# 425AK01A_S01.net
KiCad netlist of a schematic drawn in Altium Designer
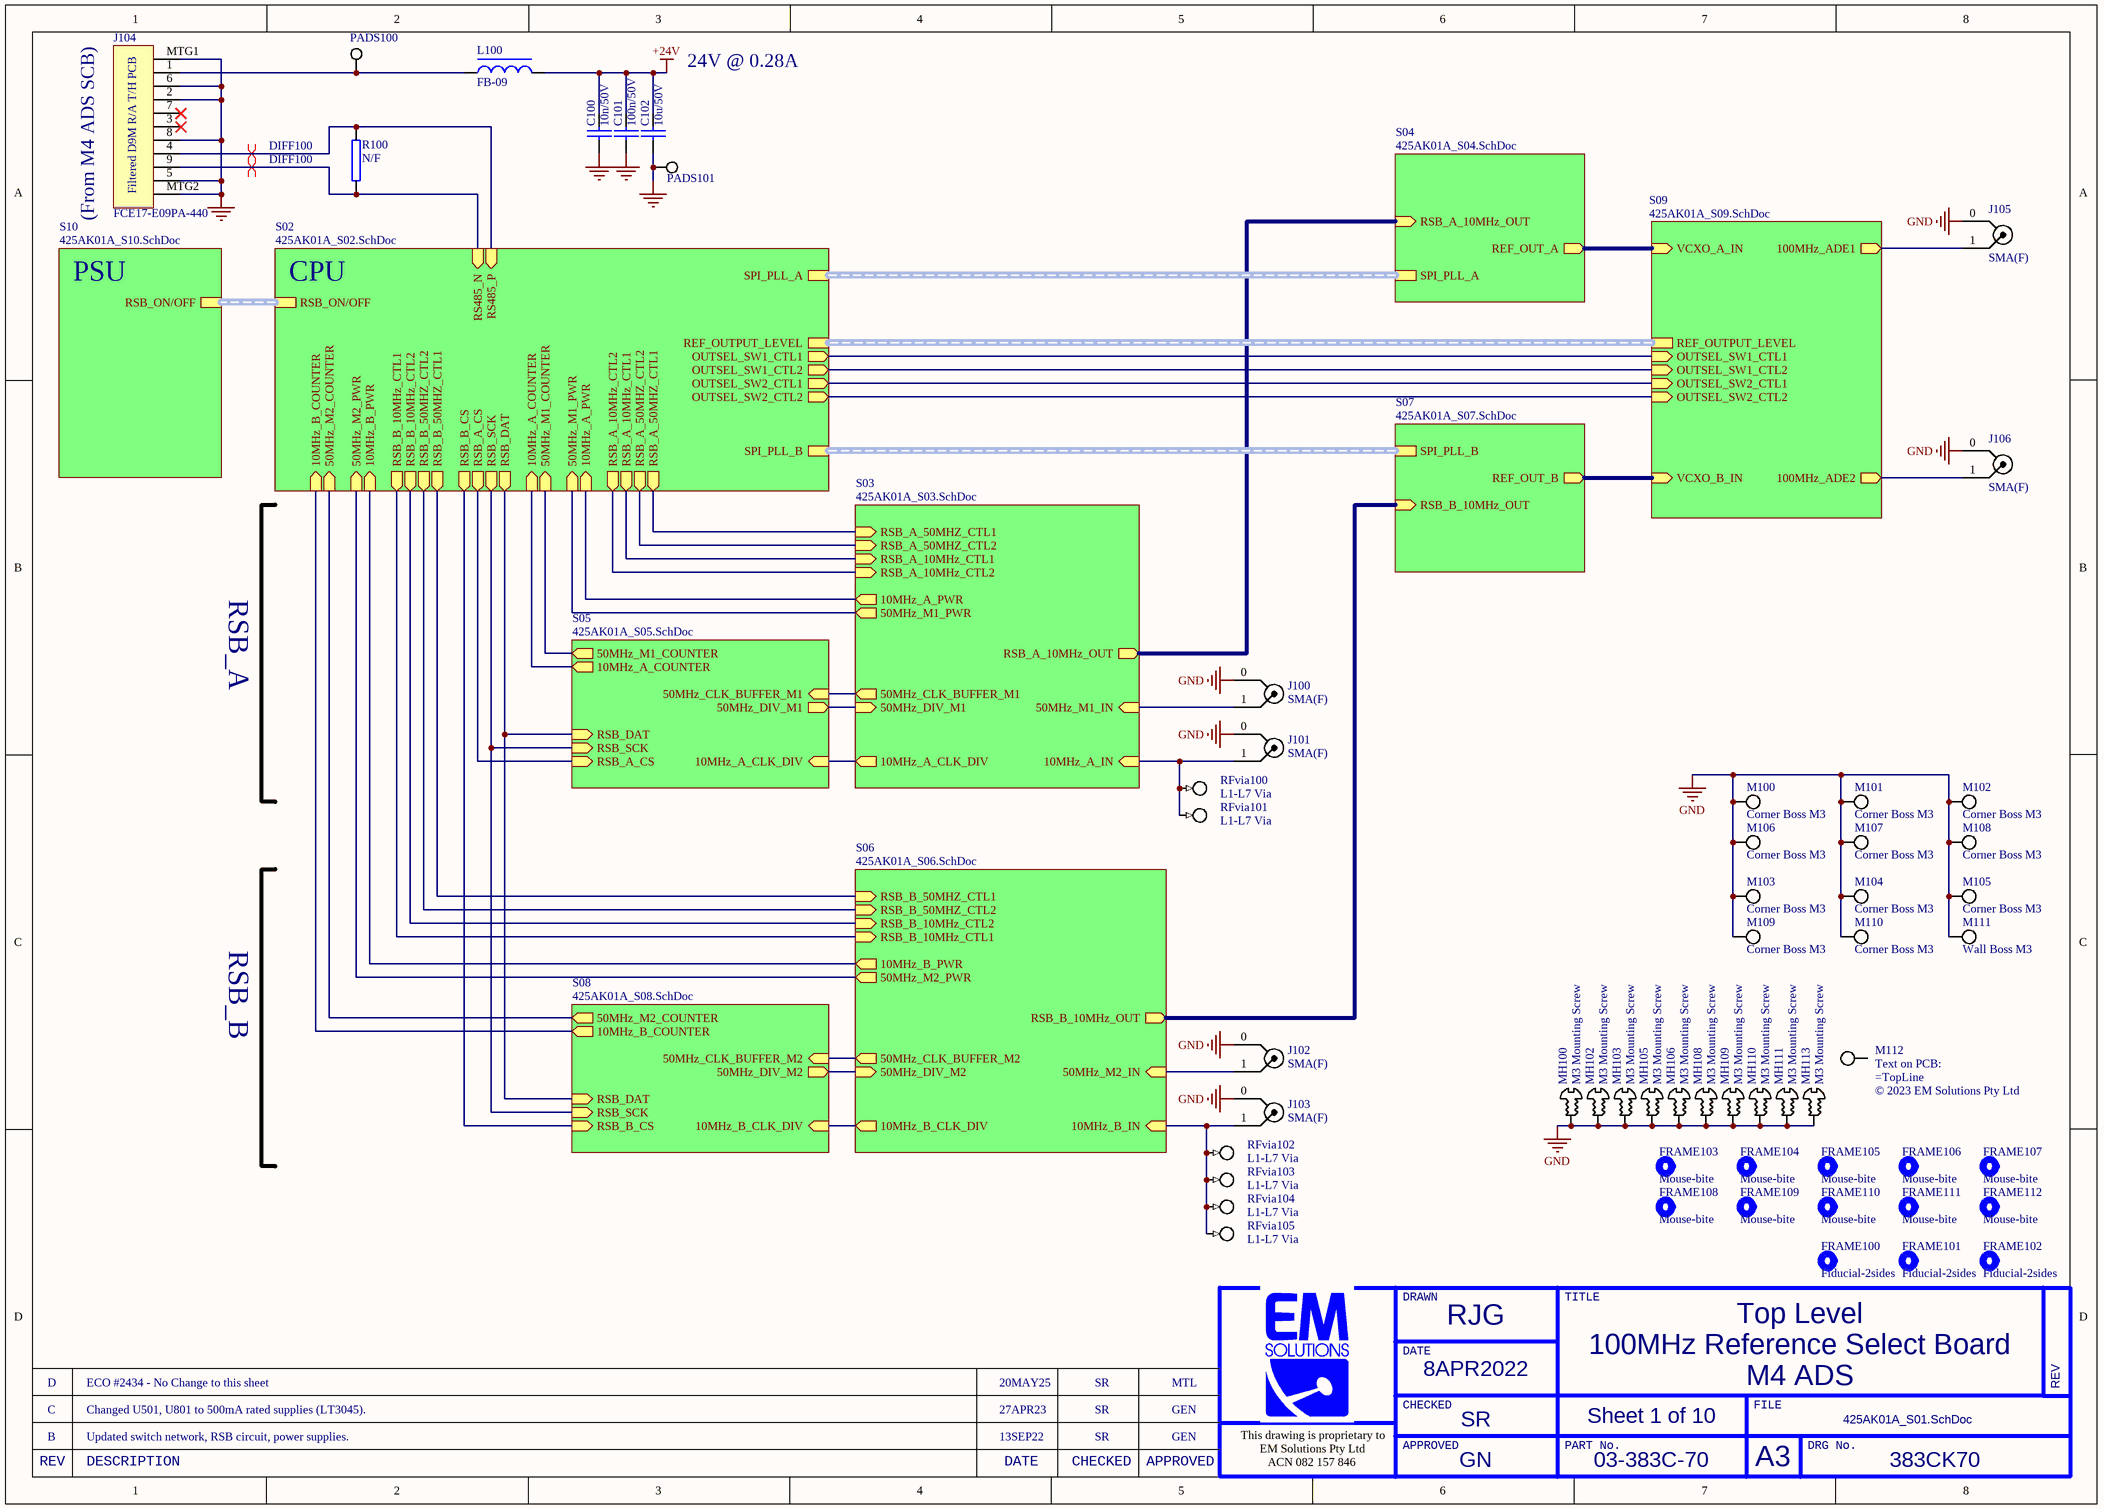
[diagram p0: 425AK01A_S01.SchDoc]

(export (version "E")
  (design (tool "Eeschema 10.0.6"))
  (components
    (comp (ref "C100")
      (value "10n/50V")
      (footprint "0402C")
      (description "Capacitor, 0402, 10n X7R 10% 50V Ceramic, NiSn")
      (fields (field (name "PART NUMBER") "41-010N-12") (field (name "MANUFACTURER") "MURATA"))
      (libsource (lib "EM DFM Library") (part "CAP"))
    )
    (comp (ref "C101")
      (value "100n/50V")
      (footprint "0402C")
      (description "Capacitor, 0402, 100n, X7R, 10% 50V, Ceramic")
      (fields (field (name "PART NUMBER") "41-100N-13") (field (name "MANUFACTURER") "MURATA"))
      (libsource (lib "EM DFM Library") (part "CAP"))
    )
    (comp (ref "C102")
      (value "10u/50V")
      (footprint "1206C")
      (description "Capacitor, 1206, 10u X7R 10% 50V Ceramic, NiSn")
      (fields (field (name "PART NUMBER") "41-010U-13") (field (name "MANUFACTURER") "SAMSUNG"))
      (libsource (lib "EM DFM Library") (part "CAP"))
    )
    (comp (ref "FRAME100")
      (value "Fiducial-2sides")
      (footprint "Fiducial-2layers")
      (description "Fiducial on both sides of the PCB")
      (libsource (lib "Russell") (part "Fiducial-2sides"))
    )
    (comp (ref "FRAME101")
      (value "Fiducial-2sides")
      (footprint "Fiducial-2layers")
      (description "Fiducial on both sides of the PCB")
      (libsource (lib "Russell") (part "Fiducial-2sides"))
    )
    (comp (ref "FRAME102")
      (value "Fiducial-2sides")
      (footprint "Fiducial-2layers")
      (description "Fiducial on both sides of the PCB")
      (libsource (lib "Russell") (part "Fiducial-2sides"))
    )
    (comp (ref "FRAME103")
      (value "Mouse-bite")
      (footprint "Breakout-3hole")
      (description "Add design rule:\r\nBoardOutlineClearance_Breakouts, name like 'FRAME*-NoDRC', 0")
      (libsource (lib "Russell") (part "Breakout"))
    )
    (comp (ref "FRAME104")
      (value "Mouse-bite")
      (footprint "Breakout-3hole")
      (description "Add design rule:\r\nBoardOutlineClearance_Breakouts, name like 'FRAME*-NoDRC', 0")
      (libsource (lib "Russell") (part "Breakout"))
    )
    (comp (ref "FRAME105")
      (value "Mouse-bite")
      (footprint "Breakout-3hole")
      (description "Add design rule:\r\nBoardOutlineClearance_Breakouts, name like 'FRAME*-NoDRC', 0")
      (libsource (lib "Russell") (part "Breakout"))
    )
    (comp (ref "FRAME106")
      (value "Mouse-bite")
      (footprint "Breakout-3hole")
      (description "Add design rule:\r\nBoardOutlineClearance_Breakouts, name like 'FRAME*-NoDRC', 0")
      (libsource (lib "Russell") (part "Breakout"))
    )
    (comp (ref "FRAME107")
      (value "Mouse-bite")
      (footprint "Breakout-3hole")
      (description "Add design rule:\r\nBoardOutlineClearance_Breakouts, name like 'FRAME*-NoDRC', 0")
      (libsource (lib "Russell") (part "Breakout"))
    )
    (comp (ref "FRAME108")
      (value "Mouse-bite")
      (footprint "Breakout-3hole")
      (description "Add design rule:\r\nBoardOutlineClearance_Breakouts, name like 'FRAME*-NoDRC', 0")
      (libsource (lib "Russell") (part "Breakout"))
    )
    (comp (ref "FRAME109")
      (value "Mouse-bite")
      (footprint "Breakout-3hole")
      (description "Add design rule:\r\nBoardOutlineClearance_Breakouts, name like 'FRAME*-NoDRC', 0")
      (libsource (lib "Russell") (part "Breakout"))
    )
    (comp (ref "FRAME110")
      (value "Mouse-bite")
      (footprint "Breakout-3hole")
      (description "Add design rule:\r\nBoardOutlineClearance_Breakouts, name like 'FRAME*-NoDRC', 0")
      (libsource (lib "Russell") (part "Breakout"))
    )
    (comp (ref "FRAME111")
      (value "Mouse-bite")
      (footprint "Breakout-3hole")
      (description "Add design rule:\r\nBoardOutlineClearance_Breakouts, name like 'FRAME*-NoDRC', 0")
      (libsource (lib "Russell") (part "Breakout"))
    )
    (comp (ref "FRAME112")
      (value "Mouse-bite")
      (footprint "Breakout-3hole")
      (description "Add design rule:\r\nBoardOutlineClearance_Breakouts, name like 'FRAME*-NoDRC', 0")
      (libsource (lib "Russell") (part "Breakout"))
    )
    (comp (ref "J100")
      (value "SMA(F)")
      (footprint "SMA-flange-generic")
      (description "Generic SMA bulkhead connector. Grounding via chassis.")
      (fields (field (name "PART NUMBER") "30-P-01"))
      (libsource (lib "Russell") (part "Connector-SMA-edge"))
    )
    (comp (ref "J101")
      (value "SMA(F)")
      (footprint "SMA-flange-generic")
      (description "Generic SMA bulkhead connector. Grounding via chassis.")
      (fields (field (name "PART NUMBER") "30-P-01"))
      (libsource (lib "Russell") (part "Connector-SMA-edge"))
    )
    (comp (ref "J102")
      (value "SMA(F)")
      (footprint "SMA-flange-generic")
      (description "Generic SMA bulkhead connector. Grounding via chassis.")
      (fields (field (name "PART NUMBER") "30-P-01"))
      (libsource (lib "Russell") (part "Connector-SMA-edge"))
    )
    (comp (ref "J103")
      (value "SMA(F)")
      (footprint "SMA-flange-generic")
      (description "Generic SMA bulkhead connector. Grounding via chassis.")
      (fields (field (name "PART NUMBER") "30-P-01"))
      (libsource (lib "Russell") (part "Connector-SMA-edge"))
    )
    (comp (ref "J104")
      (value "FCE17-E09PA-440")
      (footprint "Connector-D9-M-Filtered-T/H")
      (description "Amphenol FCE17-E09PA-440 D9M Filtered R/A T/H connector")
      (fields (field (name "PART NUMBER") "20-D9-10"))
      (libsource (lib "Russell") (part "Connector-D9-M-Filtered-T/H_PCBorder"))
    )
    (comp (ref "J105")
      (value "SMA(F)")
      (footprint "SMA-flange-generic")
      (description "Generic SMA bulkhead connector. Grounding via chassis.")
      (fields (field (name "PART NUMBER") "30-P-01"))
      (libsource (lib "Russell") (part "Connector-SMA-edge"))
    )
    (comp (ref "J106")
      (value "SMA(F)")
      (footprint "SMA-flange-generic")
      (description "Generic SMA bulkhead connector. Grounding via chassis.")
      (fields (field (name "PART NUMBER") "30-P-01"))
      (libsource (lib "Russell") (part "Connector-SMA-edge"))
    )
    (comp (ref "L100")
      (value "FB-09")
      (footprint "0805L")
      (description "Solid Inductor, 1000ohm@100MHz, DCR=0.15, 1A, 0805 size")
      (fields (field (name "PART NUMBER") "46-B-09") (field (name "MANUFACTURER") "LAIRD"))
      (libsource (lib "EM DFM Library") (part "IND"))
    )
    (comp (ref "M100")
      (value "Corner Boss M3")
      (footprint "Boss-corner-M3")
      (libsource (lib "Russell") (part "Boss-Corner-M3"))
    )
    (comp (ref "M101")
      (value "Corner Boss M3")
      (footprint "Boss-corner-M3")
      (libsource (lib "Russell") (part "Boss-Corner-M3"))
    )
    (comp (ref "M102")
      (value "Corner Boss M3")
      (footprint "Boss-corner-M3-rev")
      (libsource (lib "Russell") (part "Boss-Corner-M3"))
    )
    (comp (ref "M103")
      (value "Corner Boss M3")
      (footprint "Boss-corner-M3-rev")
      (libsource (lib "Russell") (part "Boss-Corner-M3"))
    )
    (comp (ref "M104")
      (value "Corner Boss M3")
      (footprint "Boss-corner-M3")
      (libsource (lib "Russell") (part "Boss-Corner-M3"))
    )
    (comp (ref "M105")
      (value "Corner Boss M3")
      (footprint "Boss-corner-M3-rev")
      (libsource (lib "Russell") (part "Boss-Corner-M3"))
    )
    (comp (ref "M106")
      (value "Corner Boss M3")
      (footprint "Boss-corner-M3")
      (libsource (lib "Russell") (part "Boss-Corner-M3"))
    )
    (comp (ref "M107")
      (value "Corner Boss M3")
      (footprint "Boss-corner-M3")
      (libsource (lib "Russell") (part "Boss-Corner-M3"))
    )
    (comp (ref "M108")
      (value "Corner Boss M3")
      (footprint "Boss-corner-M3")
      (libsource (lib "Russell") (part "Boss-Corner-M3"))
    )
    (comp (ref "M109")
      (value "Corner Boss M3")
      (footprint "Boss-corner-M3")
      (libsource (lib "Russell") (part "Boss-Corner-M3"))
    )
    (comp (ref "M110")
      (value "Corner Boss M3")
      (footprint "Boss-corner-M3")
      (libsource (lib "Russell") (part "Boss-Corner-M3"))
    )
    (comp (ref "M111")
      (value "Wall Boss M3")
      (footprint "Boss-Wall")
      (libsource (lib "Russell") (part "Boss-M3-Wall"))
    )
    (comp (ref "M112")
      (value "Text on PCB:")
      (footprint "PCB-title-V2-3mm")
      (libsource (lib "Russell") (part "Title of PCB"))
    )
    (comp (ref "MH100")
      (value "M3 Mounting Screw")
      (footprint "M3_SCREW")
      (libsource (lib "Russell") (part "M3 Screw"))
    )
    (comp (ref "MH102")
      (value "M3 Mounting Screw")
      (footprint "M3_SCREW")
      (libsource (lib "Russell") (part "M3 Screw"))
    )
    (comp (ref "MH103")
      (value "M3 Mounting Screw")
      (footprint "M3_SCREW")
      (libsource (lib "Russell") (part "M3 Screw"))
    )
    (comp (ref "MH105")
      (value "M3 Mounting Screw")
      (footprint "M3_SCREW")
      (libsource (lib "Russell") (part "M3 Screw"))
    )
    (comp (ref "MH106")
      (value "M3 Mounting Screw")
      (footprint "M3_SCREW")
      (libsource (lib "Russell") (part "M3 Screw"))
    )
    (comp (ref "MH108")
      (value "M3 Mounting Screw")
      (footprint "M3_SCREW")
      (libsource (lib "Russell") (part "M3 Screw"))
    )
    (comp (ref "MH109")
      (value "M3 Mounting Screw")
      (footprint "M3_SCREW")
      (libsource (lib "Russell") (part "M3 Screw"))
    )
    (comp (ref "MH110")
      (value "M3 Mounting Screw")
      (footprint "M3_SCREW")
      (libsource (lib "Russell") (part "M3 Screw"))
    )
    (comp (ref "MH111")
      (value "M3 Mounting Screw")
      (footprint "M3_SCREW")
      (libsource (lib "Russell") (part "M3 Screw"))
    )
    (comp (ref "MH113")
      (value "M3 Mounting Screw")
      (footprint "M3_SCREW")
      (libsource (lib "Russell") (part "M3 Screw"))
    )
    (comp (ref "PADS100")
      (value "Pads")
      (footprint "Pads-1x3-V3-0.3/0.6mm")
      (description "Cluster of pads")
      (libsource (lib "Russell") (part "Pads"))
    )
    (comp (ref "PADS101")
      (value "Pads")
      (footprint "Pads-1x3-V3-0.3/0.6mm")
      (description "Cluster of pads")
      (libsource (lib "Russell") (part "Pads"))
    )
    (comp (ref "R100")
      (value "N/F")
      (footprint "0805")
      (description "Resistor, 0805, SOT, Not Fitted")
      (fields (field (name "PART NUMBER") "44-N/F-09") (field (name "MANUFACTURER") "PHILIPS"))
      (libsource (lib "EM DFM Library") (part "RES"))
    )
    (comp (ref "RFvia100")
      (value "L1-L7 Via")
      (footprint "RFvia_L1-L7")
      (description "RF Via from layer 1 to layer 7, on an 8-layer board.")
      (libsource (lib "RFvias-8layer") (part "RFvia_L1-L7"))
    )
    (comp (ref "RFvia101")
      (value "L1-L7 Via")
      (footprint "RFvia_L1-L7")
      (description "RF Via from layer 1 to layer 7, on an 8-layer board.")
      (libsource (lib "RFvias-8layer") (part "RFvia_L1-L7"))
    )
    (comp (ref "RFvia102")
      (value "L1-L7 Via")
      (footprint "RFvia_L1-L7")
      (description "RF Via from layer 1 to layer 7, on an 8-layer board.")
      (libsource (lib "RFvias-8layer") (part "RFvia_L1-L7"))
    )
    (comp (ref "RFvia103")
      (value "L1-L7 Via")
      (footprint "RFvia_L1-L7")
      (description "RF Via from layer 1 to layer 7, on an 8-layer board.")
      (libsource (lib "RFvias-8layer") (part "RFvia_L1-L7"))
    )
    (comp (ref "RFvia104")
      (value "L1-L7 Via")
      (footprint "RFvia_L1-L7")
      (description "RF Via from layer 1 to layer 7, on an 8-layer board.")
      (libsource (lib "RFvias-8layer") (part "RFvia_L1-L7"))
    )
    (comp (ref "RFvia105")
      (value "L1-L7 Via")
      (footprint "RFvia_L1-L7")
      (description "RF Via from layer 1 to layer 7, on an 8-layer board.")
      (libsource (lib "RFvias-8layer") (part "RFvia_L1-L7"))
    )
  )
  (nets
    (net (code "1") (name "+24V") (class "Default")
      (node (ref "C100") (pin "1") (pintype "passive"))
      (node (ref "C101") (pin "1") (pintype "passive"))
      (node (ref "C102") (pin "1") (pintype "passive"))
      (node (ref "L100") (pin "2") (pinfunction "2_2") (pintype "passive"))
    )
    (net (code "4") (name "/10MHz_A_IN") (class "Default")
      (node (ref "J101") (pin "1") (pinfunction "1_1") (pintype "passive"))
      (node (ref "RFvia100") (pin "1") (pinfunction "1_1") (pintype "input"))
      (node (ref "RFvia101") (pin "1") (pinfunction "1_1") (pintype "input"))
    )
    (net (code "8") (name "/10MHz_B_IN") (class "Default")
      (node (ref "J103") (pin "1") (pinfunction "1_1") (pintype "passive"))
      (node (ref "RFvia102") (pin "1") (pinfunction "1_1") (pintype "input"))
      (node (ref "RFvia103") (pin "1") (pinfunction "1_1") (pintype "input"))
      (node (ref "RFvia104") (pin "1") (pinfunction "1_1") (pintype "input"))
      (node (ref "RFvia105") (pin "1") (pinfunction "1_1") (pintype "input"))
    )
    (net (code "15") (name "/50MHz_M1_IN") (class "Default")
      (node (ref "J100") (pin "1") (pinfunction "1_1") (pintype "passive"))
    )
    (net (code "18") (name "/50MHz_M2_IN") (class "Default")
      (node (ref "J102") (pin "1") (pinfunction "1_1") (pintype "passive"))
    )
    (net (code "20") (name "/100MHz_ADE1") (class "Default")
      (node (ref "J105") (pin "1") (pinfunction "1_1") (pintype "passive"))
    )
    (net (code "21") (name "/100MHz_ADE2") (class "Default")
      (node (ref "J106") (pin "1") (pinfunction "1_1") (pintype "passive"))
    )
    (net (code "29") (name "/RS485_N") (class "Default")
      (node (ref "J104") (pin "9") (pinfunction "9_9") (pintype "passive"))
      (node (ref "R100") (pin "1") (pintype "passive"))
    )
    (net (code "30") (name "/RS485_P") (class "Default")
      (node (ref "J104") (pin "4") (pinfunction "4_4") (pintype "passive"))
      (node (ref "R100") (pin "2") (pintype "passive"))
    )
    (net (code "48") (name "GND") (class "Default")
      (node (ref "C100") (pin "2") (pintype "passive"))
      (node (ref "C101") (pin "2") (pintype "passive"))
      (node (ref "C102") (pin "2") (pintype "passive"))
      (node (ref "J100") (pin "0") (pinfunction "0_0") (pintype "passive"))
      (node (ref "J101") (pin "0") (pinfunction "0_0") (pintype "passive"))
      (node (ref "J102") (pin "0") (pinfunction "0_0") (pintype "passive"))
      (node (ref "J103") (pin "0") (pinfunction "0_0") (pintype "passive"))
      (node (ref "J104") (pin "2") (pinfunction "2_2") (pintype "passive"))
      (node (ref "J104") (pin "5") (pinfunction "5_5") (pintype "passive"))
      (node (ref "J104") (pin "6") (pinfunction "6_6") (pintype "passive"))
      (node (ref "J104") (pin "8") (pinfunction "8_8") (pintype "passive"))
      (node (ref "J104") (pin "MTG1") (pinfunction "MTG1_MTG1") (pintype "passive"))
      (node (ref "J104") (pin "MTG2") (pinfunction "MTG2_MTG2") (pintype "passive"))
      (node (ref "J105") (pin "0") (pinfunction "0_0") (pintype "passive"))
      (node (ref "J106") (pin "0") (pinfunction "0_0") (pintype "passive"))
      (node (ref "M100") (pin "1") (pinfunction "1_1") (pintype "passive"))
      (node (ref "M101") (pin "1") (pinfunction "1_1") (pintype "passive"))
      (node (ref "M102") (pin "1") (pinfunction "1_1") (pintype "passive"))
      (node (ref "M103") (pin "1") (pinfunction "1_1") (pintype "passive"))
      (node (ref "M104") (pin "1") (pinfunction "1_1") (pintype "passive"))
      (node (ref "M105") (pin "1") (pinfunction "1_1") (pintype "passive"))
      (node (ref "M106") (pin "1") (pinfunction "1_1") (pintype "passive"))
      (node (ref "M107") (pin "1") (pinfunction "1_1") (pintype "passive"))
      (node (ref "M108") (pin "1") (pinfunction "1_1") (pintype "passive"))
      (node (ref "M109") (pin "1") (pinfunction "1_1") (pintype "passive"))
      (node (ref "M110") (pin "1") (pinfunction "1_1") (pintype "passive"))
      (node (ref "M111") (pin "1") (pinfunction "1_1") (pintype "passive"))
      (node (ref "MH100") (pin "1") (pinfunction "1_1") (pintype "passive"))
      (node (ref "MH102") (pin "1") (pinfunction "1_1") (pintype "passive"))
      (node (ref "MH103") (pin "1") (pinfunction "1_1") (pintype "passive"))
      (node (ref "MH105") (pin "1") (pinfunction "1_1") (pintype "passive"))
      (node (ref "MH106") (pin "1") (pinfunction "1_1") (pintype "passive"))
      (node (ref "MH108") (pin "1") (pinfunction "1_1") (pintype "passive"))
      (node (ref "MH109") (pin "1") (pinfunction "1_1") (pintype "passive"))
      (node (ref "MH110") (pin "1") (pinfunction "1_1") (pintype "passive"))
      (node (ref "MH111") (pin "1") (pinfunction "1_1") (pintype "passive"))
      (node (ref "MH113") (pin "1") (pinfunction "1_1") (pintype "passive"))
      (node (ref "PADS101") (pin "1") (pinfunction "1_1") (pintype "passive"))
    )
    (net (code "49") (name "Net-(J104-Pad1)") (class "Default")
      (node (ref "J104") (pin "1") (pinfunction "1_1") (pintype "passive"))
      (node (ref "L100") (pin "1") (pinfunction "1_1") (pintype "passive"))
      (node (ref "PADS100") (pin "1") (pinfunction "1_1") (pintype "passive"))
    )
    (net (code "50") (name "unconnected-(J104-Pad3)") (class "Default")
      (node (ref "J104") (pin "3") (pinfunction "3_3") (pintype "passive+no_connect"))
    )
    (net (code "51") (name "unconnected-(J104-Pad7)") (class "Default")
      (node (ref "J104") (pin "7") (pinfunction "7_7") (pintype "passive+no_connect"))
    )
    (net (code "52") (name "unconnected-(M112-Pad1)") (class "Default")
      (node (ref "M112") (pin "1") (pinfunction "1_1") (pintype "passive"))
    )
  )
)
